# CURRENT_SENSE.net
KiCad netlist of a schematic drawn in Altium Designer
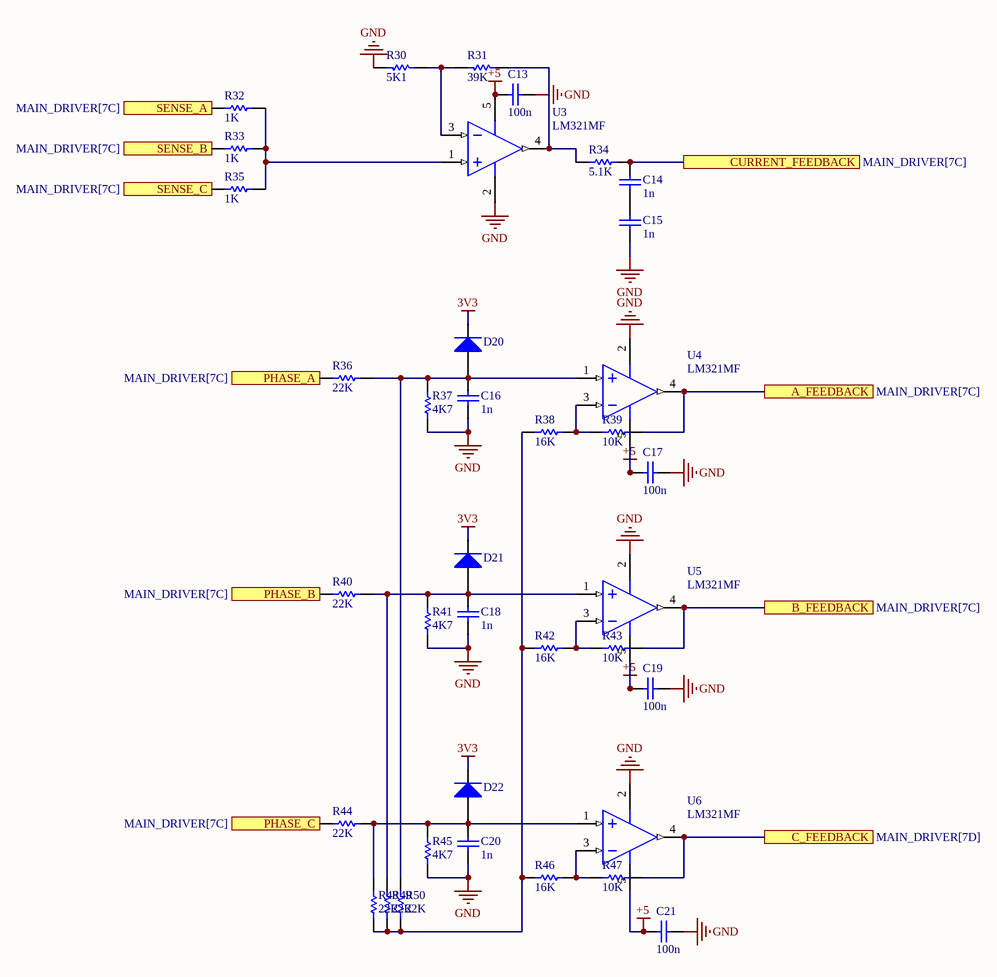
[diagram p0: CURRENT_SENSE.SchDoc]

(export (version "E")
  (design (tool "Eeschema 10.0.6"))
  (components
    (comp (ref "C13")
      (value "100n")
      (footprint "CAP FILM 0603_1608")
      (description "Capacitor")
      (libsource (lib "Simulation Generic Components") (part "Capacitor"))
    )
    (comp (ref "C14")
      (value "1n")
      (footprint "CAP FILM 0603_1608")
      (description "Capacitor")
      (libsource (lib "Simulation Generic Components") (part "Capacitor"))
    )
    (comp (ref "C15")
      (value "1n")
      (footprint "CAP FILM 0603_1608")
      (description "Capacitor")
      (libsource (lib "Simulation Generic Components") (part "Capacitor"))
    )
    (comp (ref "C16")
      (value "1n")
      (footprint "CAP FILM 0603_1608")
      (description "Capacitor")
      (libsource (lib "Simulation Generic Components") (part "Capacitor"))
    )
    (comp (ref "C17")
      (value "100n")
      (footprint "CAP FILM 0603_1608")
      (description "Capacitor")
      (libsource (lib "Simulation Generic Components") (part "Capacitor"))
    )
    (comp (ref "C18")
      (value "1n")
      (footprint "CAP FILM 0603_1608")
      (description "Capacitor")
      (libsource (lib "Simulation Generic Components") (part "Capacitor"))
    )
    (comp (ref "C19")
      (value "100n")
      (footprint "CAP FILM 0603_1608")
      (description "Capacitor")
      (libsource (lib "Simulation Generic Components") (part "Capacitor"))
    )
    (comp (ref "C20")
      (value "1n")
      (footprint "CAP FILM 0603_1608")
      (description "Capacitor")
      (libsource (lib "Simulation Generic Components") (part "Capacitor"))
    )
    (comp (ref "C21")
      (value "100n")
      (footprint "CAP FILM 0603_1608")
      (description "Capacitor")
      (libsource (lib "Simulation Generic Components") (part "Capacitor"))
    )
    (comp (ref "D20")
      (value "1N4148W")
      (footprint "SODFL375X135-2N")
      (description "Diode")
      (libsource (lib "Simulation Generic Components") (part "Diode"))
    )
    (comp (ref "D21")
      (value "1N4148W")
      (footprint "SODFL375X135-2N")
      (description "Diode")
      (libsource (lib "Simulation Generic Components") (part "Diode"))
    )
    (comp (ref "D22")
      (value "1N4148W")
      (footprint "SODFL375X135-2N")
      (description "Diode")
      (libsource (lib "Simulation Generic Components") (part "Diode"))
    )
    (comp (ref "R30")
      (value "5K1")
      (footprint "RES 0603_1608 RF")
      (description "Resistor")
      (libsource (lib "Simulation Generic Components") (part "Resistor"))
    )
    (comp (ref "R31")
      (value "39K")
      (footprint "RES 0603_1608 RF")
      (description "Resistor")
      (libsource (lib "Simulation Generic Components") (part "Resistor"))
    )
    (comp (ref "R32")
      (value "1K")
      (footprint "RES 0603_1608 RF")
      (description "Resistor")
      (libsource (lib "Simulation Generic Components") (part "Resistor"))
    )
    (comp (ref "R33")
      (value "1K")
      (footprint "RES 0603_1608 RF")
      (description "Resistor")
      (libsource (lib "Simulation Generic Components") (part "Resistor"))
    )
    (comp (ref "R34")
      (value "5.1K")
      (footprint "RES 0603_1608 RF")
      (description "Resistor")
      (libsource (lib "Simulation Generic Components") (part "Resistor"))
    )
    (comp (ref "R35")
      (value "1K")
      (footprint "RES 0603_1608 RF")
      (description "Resistor")
      (libsource (lib "Simulation Generic Components") (part "Resistor"))
    )
    (comp (ref "R36")
      (value "22K")
      (footprint "RES 0603_1608 RF")
      (description "Resistor")
      (libsource (lib "Simulation Generic Components") (part "Resistor"))
    )
    (comp (ref "R37")
      (value "4K7")
      (footprint "RES 0603_1608 RF")
      (description "Resistor")
      (libsource (lib "Simulation Generic Components") (part "Resistor"))
    )
    (comp (ref "R38")
      (value "16K")
      (footprint "RES 0603_1608 RF")
      (description "Resistor")
      (libsource (lib "Simulation Generic Components") (part "Resistor"))
    )
    (comp (ref "R39")
      (value "10K")
      (footprint "RES 0603_1608 RF")
      (description "Resistor")
      (libsource (lib "Simulation Generic Components") (part "Resistor"))
    )
    (comp (ref "R40")
      (value "22K")
      (footprint "RES 0603_1608 RF")
      (description "Resistor")
      (libsource (lib "Simulation Generic Components") (part "Resistor"))
    )
    (comp (ref "R41")
      (value "4K7")
      (footprint "RES 0603_1608 RF")
      (description "Resistor")
      (libsource (lib "Simulation Generic Components") (part "Resistor"))
    )
    (comp (ref "R42")
      (value "16K")
      (footprint "RES 0603_1608 RF")
      (description "Resistor")
      (libsource (lib "Simulation Generic Components") (part "Resistor"))
    )
    (comp (ref "R43")
      (value "10K")
      (footprint "RES 0603_1608 RF")
      (description "Resistor")
      (libsource (lib "Simulation Generic Components") (part "Resistor"))
    )
    (comp (ref "R44")
      (value "22K")
      (footprint "RES 0603_1608 RF")
      (description "Resistor")
      (libsource (lib "Simulation Generic Components") (part "Resistor"))
    )
    (comp (ref "R45")
      (value "4K7")
      (footprint "RES 0603_1608 RF")
      (description "Resistor")
      (libsource (lib "Simulation Generic Components") (part "Resistor"))
    )
    (comp (ref "R46")
      (value "16K")
      (footprint "RES 0603_1608 RF")
      (description "Resistor")
      (libsource (lib "Simulation Generic Components") (part "Resistor"))
    )
    (comp (ref "R47")
      (value "10K")
      (footprint "RES 0603_1608 RF")
      (description "Resistor")
      (libsource (lib "Simulation Generic Components") (part "Resistor"))
    )
    (comp (ref "R48")
      (value "22K")
      (footprint "RES 0603_1608 RF")
      (description "Resistor")
      (libsource (lib "Simulation Generic Components") (part "Resistor"))
    )
    (comp (ref "R49")
      (value "22K")
      (footprint "RES 0603_1608 RF")
      (description "Resistor")
      (libsource (lib "Simulation Generic Components") (part "Resistor"))
    )
    (comp (ref "R50")
      (value "22K")
      (footprint "RES 0603_1608 RF")
      (description "Resistor")
      (libsource (lib "Simulation Generic Components") (part "Resistor"))
    )
    (comp (ref "U3")
      (value "LM321MF")
      (footprint "DBV0005A_L")
      (description "Low Power Single Op Amp, 5-pin SOT-23")
      (fields (field (name "MANUFACTURER") "Texas Instruments"))
      (libsource (lib "Altium Content Vault") (part "AMP-OPA-LMV551-5"))
    )
    (comp (ref "U4")
      (value "LM321MF")
      (footprint "DBV0005A_L")
      (description "Low Power Single Op Amp, 5-pin SOT-23")
      (fields (field (name "MANUFACTURER") "Texas Instruments"))
      (libsource (lib "Altium Content Vault") (part "AMP-OPA-LMV551-5"))
    )
    (comp (ref "U5")
      (value "LM321MF")
      (footprint "DBV0005A_L")
      (description "Low Power Single Op Amp, 5-pin SOT-23")
      (fields (field (name "MANUFACTURER") "Texas Instruments"))
      (libsource (lib "Altium Content Vault") (part "AMP-OPA-LMV551-5"))
    )
    (comp (ref "U6")
      (value "LM321MF")
      (footprint "DBV0005A_L")
      (description "Low Power Single Op Amp, 5-pin SOT-23")
      (fields (field (name "MANUFACTURER") "Texas Instruments"))
      (libsource (lib "Altium Content Vault") (part "AMP-OPA-LMV551-5"))
    )
  )
  (nets
    (net (code "1") (name "+5") (class "Default")
      (node (ref "C13") (pin "1") (pinfunction "1_1") (pintype "passive"))
      (node (ref "C17") (pin "1") (pinfunction "1_1") (pintype "passive"))
      (node (ref "C19") (pin "1") (pinfunction "1_1") (pintype "passive"))
      (node (ref "C21") (pin "1") (pinfunction "1_1") (pintype "passive"))
      (node (ref "U3") (pin "5") (pinfunction "V+_5") (pintype "power_in"))
      (node (ref "U4") (pin "5") (pinfunction "V+_5") (pintype "power_in"))
      (node (ref "U5") (pin "5") (pinfunction "V+_5") (pintype "power_in"))
      (node (ref "U6") (pin "5") (pinfunction "V+_5") (pintype "power_in"))
    )
    (net (code "2") (name "/A_FEEDBACK") (class "Default")
      (node (ref "R39") (pin "2") (pinfunction "2_2") (pintype "passive"))
      (node (ref "U4") (pin "4") (pinfunction "OUT_4") (pintype "output"))
    )
    (net (code "3") (name "/B_FEEDBACK") (class "Default")
      (node (ref "R43") (pin "2") (pinfunction "2_2") (pintype "passive"))
      (node (ref "U5") (pin "4") (pinfunction "OUT_4") (pintype "output"))
    )
    (net (code "4") (name "/CURRENT_FEEDBACK") (class "Default")
      (node (ref "C14") (pin "2") (pinfunction "2_2") (pintype "passive"))
      (node (ref "R34") (pin "2") (pinfunction "2_2") (pintype "passive"))
    )
    (net (code "5") (name "/C_FEEDBACK") (class "Default")
      (node (ref "R47") (pin "2") (pinfunction "2_2") (pintype "passive"))
      (node (ref "U6") (pin "4") (pinfunction "OUT_4") (pintype "output"))
    )
    (net (code "6") (name "/PHASE_A") (class "Default")
      (node (ref "R36") (pin "1") (pinfunction "1_1") (pintype "passive"))
    )
    (net (code "7") (name "/PHASE_B") (class "Default")
      (node (ref "R40") (pin "1") (pinfunction "1_1") (pintype "passive"))
    )
    (net (code "8") (name "/PHASE_C") (class "Default")
      (node (ref "R44") (pin "1") (pinfunction "1_1") (pintype "passive"))
    )
    (net (code "9") (name "/SENSE_A") (class "Default")
      (node (ref "R32") (pin "1") (pinfunction "1_1") (pintype "passive"))
    )
    (net (code "10") (name "/SENSE_B") (class "Default")
      (node (ref "R33") (pin "1") (pinfunction "1_1") (pintype "passive"))
    )
    (net (code "11") (name "/SENSE_C") (class "Default")
      (node (ref "R35") (pin "1") (pinfunction "1_1") (pintype "passive"))
    )
    (net (code "12") (name "3V3") (class "Default")
      (node (ref "D20") (pin "2") (pinfunction "K_2") (pintype "passive"))
      (node (ref "D21") (pin "2") (pinfunction "K_2") (pintype "passive"))
      (node (ref "D22") (pin "2") (pinfunction "K_2") (pintype "passive"))
    )
    (net (code "13") (name "GND") (class "Default")
      (node (ref "C13") (pin "2") (pinfunction "2_2") (pintype "passive"))
      (node (ref "C15") (pin "1") (pinfunction "1_1") (pintype "passive"))
      (node (ref "C16") (pin "1") (pinfunction "1_1") (pintype "passive"))
      (node (ref "C17") (pin "2") (pinfunction "2_2") (pintype "passive"))
      (node (ref "C18") (pin "1") (pinfunction "1_1") (pintype "passive"))
      (node (ref "C19") (pin "2") (pinfunction "2_2") (pintype "passive"))
      (node (ref "C20") (pin "1") (pinfunction "1_1") (pintype "passive"))
      (node (ref "C21") (pin "2") (pinfunction "2_2") (pintype "passive"))
      (node (ref "R30") (pin "2") (pinfunction "2_2") (pintype "passive"))
      (node (ref "R37") (pin "1") (pinfunction "1_1") (pintype "passive"))
      (node (ref "R41") (pin "1") (pinfunction "1_1") (pintype "passive"))
      (node (ref "R45") (pin "1") (pinfunction "1_1") (pintype "passive"))
      (node (ref "U3") (pin "2") (pinfunction "V-_2") (pintype "power_in"))
      (node (ref "U4") (pin "2") (pinfunction "V-_2") (pintype "power_in"))
      (node (ref "U5") (pin "2") (pinfunction "V-_2") (pintype "power_in"))
      (node (ref "U6") (pin "2") (pinfunction "V-_2") (pintype "power_in"))
    )
    (net (code "14") (name "Net-(C14-Pad1)") (class "Default")
      (node (ref "C14") (pin "1") (pinfunction "1_1") (pintype "passive"))
      (node (ref "C15") (pin "2") (pinfunction "2_2") (pintype "passive"))
    )
    (net (code "15") (name "Net-(D20-A)") (class "Default")
      (node (ref "C16") (pin "2") (pinfunction "2_2") (pintype "passive"))
      (node (ref "D20") (pin "1") (pinfunction "A_1") (pintype "passive"))
      (node (ref "R36") (pin "2") (pinfunction "2_2") (pintype "passive"))
      (node (ref "R37") (pin "2") (pinfunction "2_2") (pintype "passive"))
      (node (ref "R50") (pin "2") (pinfunction "2_2") (pintype "passive"))
      (node (ref "U4") (pin "1") (pinfunction "IN+_1") (pintype "input"))
    )
    (net (code "16") (name "Net-(D21-A)") (class "Default")
      (node (ref "C18") (pin "2") (pinfunction "2_2") (pintype "passive"))
      (node (ref "D21") (pin "1") (pinfunction "A_1") (pintype "passive"))
      (node (ref "R40") (pin "2") (pinfunction "2_2") (pintype "passive"))
      (node (ref "R41") (pin "2") (pinfunction "2_2") (pintype "passive"))
      (node (ref "R49") (pin "2") (pinfunction "2_2") (pintype "passive"))
      (node (ref "U5") (pin "1") (pinfunction "IN+_1") (pintype "input"))
    )
    (net (code "17") (name "Net-(D22-A)") (class "Default")
      (node (ref "C20") (pin "2") (pinfunction "2_2") (pintype "passive"))
      (node (ref "D22") (pin "1") (pinfunction "A_1") (pintype "passive"))
      (node (ref "R44") (pin "2") (pinfunction "2_2") (pintype "passive"))
      (node (ref "R45") (pin "2") (pinfunction "2_2") (pintype "passive"))
      (node (ref "R48") (pin "2") (pinfunction "2_2") (pintype "passive"))
      (node (ref "U6") (pin "1") (pinfunction "IN+_1") (pintype "input"))
    )
    (net (code "18") (name "Net-(R38-Pad1)") (class "Default")
      (node (ref "R38") (pin "1") (pinfunction "1_1") (pintype "passive"))
      (node (ref "R42") (pin "1") (pinfunction "1_1") (pintype "passive"))
      (node (ref "R46") (pin "1") (pinfunction "1_1") (pintype "passive"))
      (node (ref "R48") (pin "1") (pinfunction "1_1") (pintype "passive"))
      (node (ref "R49") (pin "1") (pinfunction "1_1") (pintype "passive"))
      (node (ref "R50") (pin "1") (pinfunction "1_1") (pintype "passive"))
    )
    (net (code "19") (name "Net-(U3-IN+)") (class "Default")
      (node (ref "R32") (pin "2") (pinfunction "2_2") (pintype "passive"))
      (node (ref "R33") (pin "2") (pinfunction "2_2") (pintype "passive"))
      (node (ref "R35") (pin "2") (pinfunction "2_2") (pintype "passive"))
      (node (ref "U3") (pin "1") (pinfunction "IN+_1") (pintype "input"))
    )
    (net (code "20") (name "Net-(U3-IN-)") (class "Default")
      (node (ref "R30") (pin "1") (pinfunction "1_1") (pintype "passive"))
      (node (ref "R31") (pin "1") (pinfunction "1_1") (pintype "passive"))
      (node (ref "U3") (pin "3") (pinfunction "IN-_3") (pintype "input"))
    )
    (net (code "21") (name "Net-(U3-OUT)") (class "Default")
      (node (ref "R31") (pin "2") (pinfunction "2_2") (pintype "passive"))
      (node (ref "R34") (pin "1") (pinfunction "1_1") (pintype "passive"))
      (node (ref "U3") (pin "4") (pinfunction "OUT_4") (pintype "output"))
    )
    (net (code "22") (name "Net-(U4-IN-)") (class "Default")
      (node (ref "R38") (pin "2") (pinfunction "2_2") (pintype "passive"))
      (node (ref "R39") (pin "1") (pinfunction "1_1") (pintype "passive"))
      (node (ref "U4") (pin "3") (pinfunction "IN-_3") (pintype "input"))
    )
    (net (code "23") (name "Net-(U5-IN-)") (class "Default")
      (node (ref "R42") (pin "2") (pinfunction "2_2") (pintype "passive"))
      (node (ref "R43") (pin "1") (pinfunction "1_1") (pintype "passive"))
      (node (ref "U5") (pin "3") (pinfunction "IN-_3") (pintype "input"))
    )
    (net (code "24") (name "Net-(U6-IN-)") (class "Default")
      (node (ref "R46") (pin "2") (pinfunction "2_2") (pintype "passive"))
      (node (ref "R47") (pin "1") (pinfunction "1_1") (pintype "passive"))
      (node (ref "U6") (pin "3") (pinfunction "IN-_3") (pintype "input"))
    )
  )
)
